# Dyno_Tiva_Shield.net
KiCad netlist of a schematic drawn in EAGLE
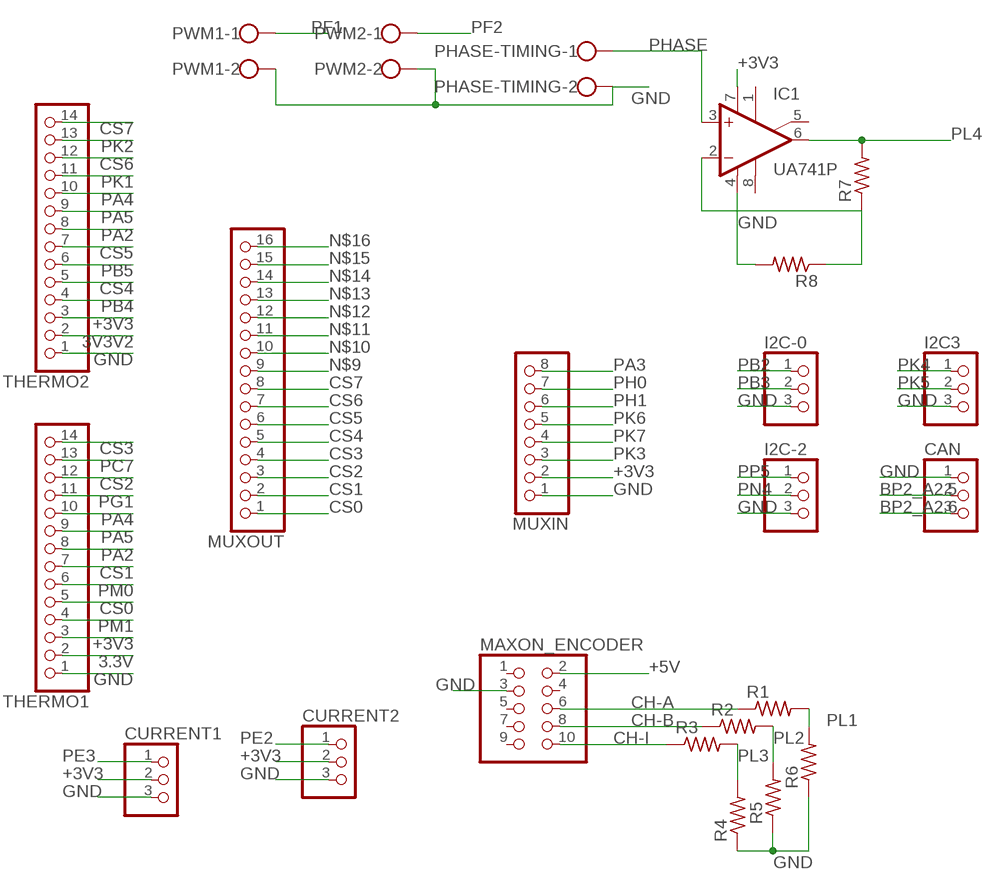
[diagram p0: schematic, sheet 1]
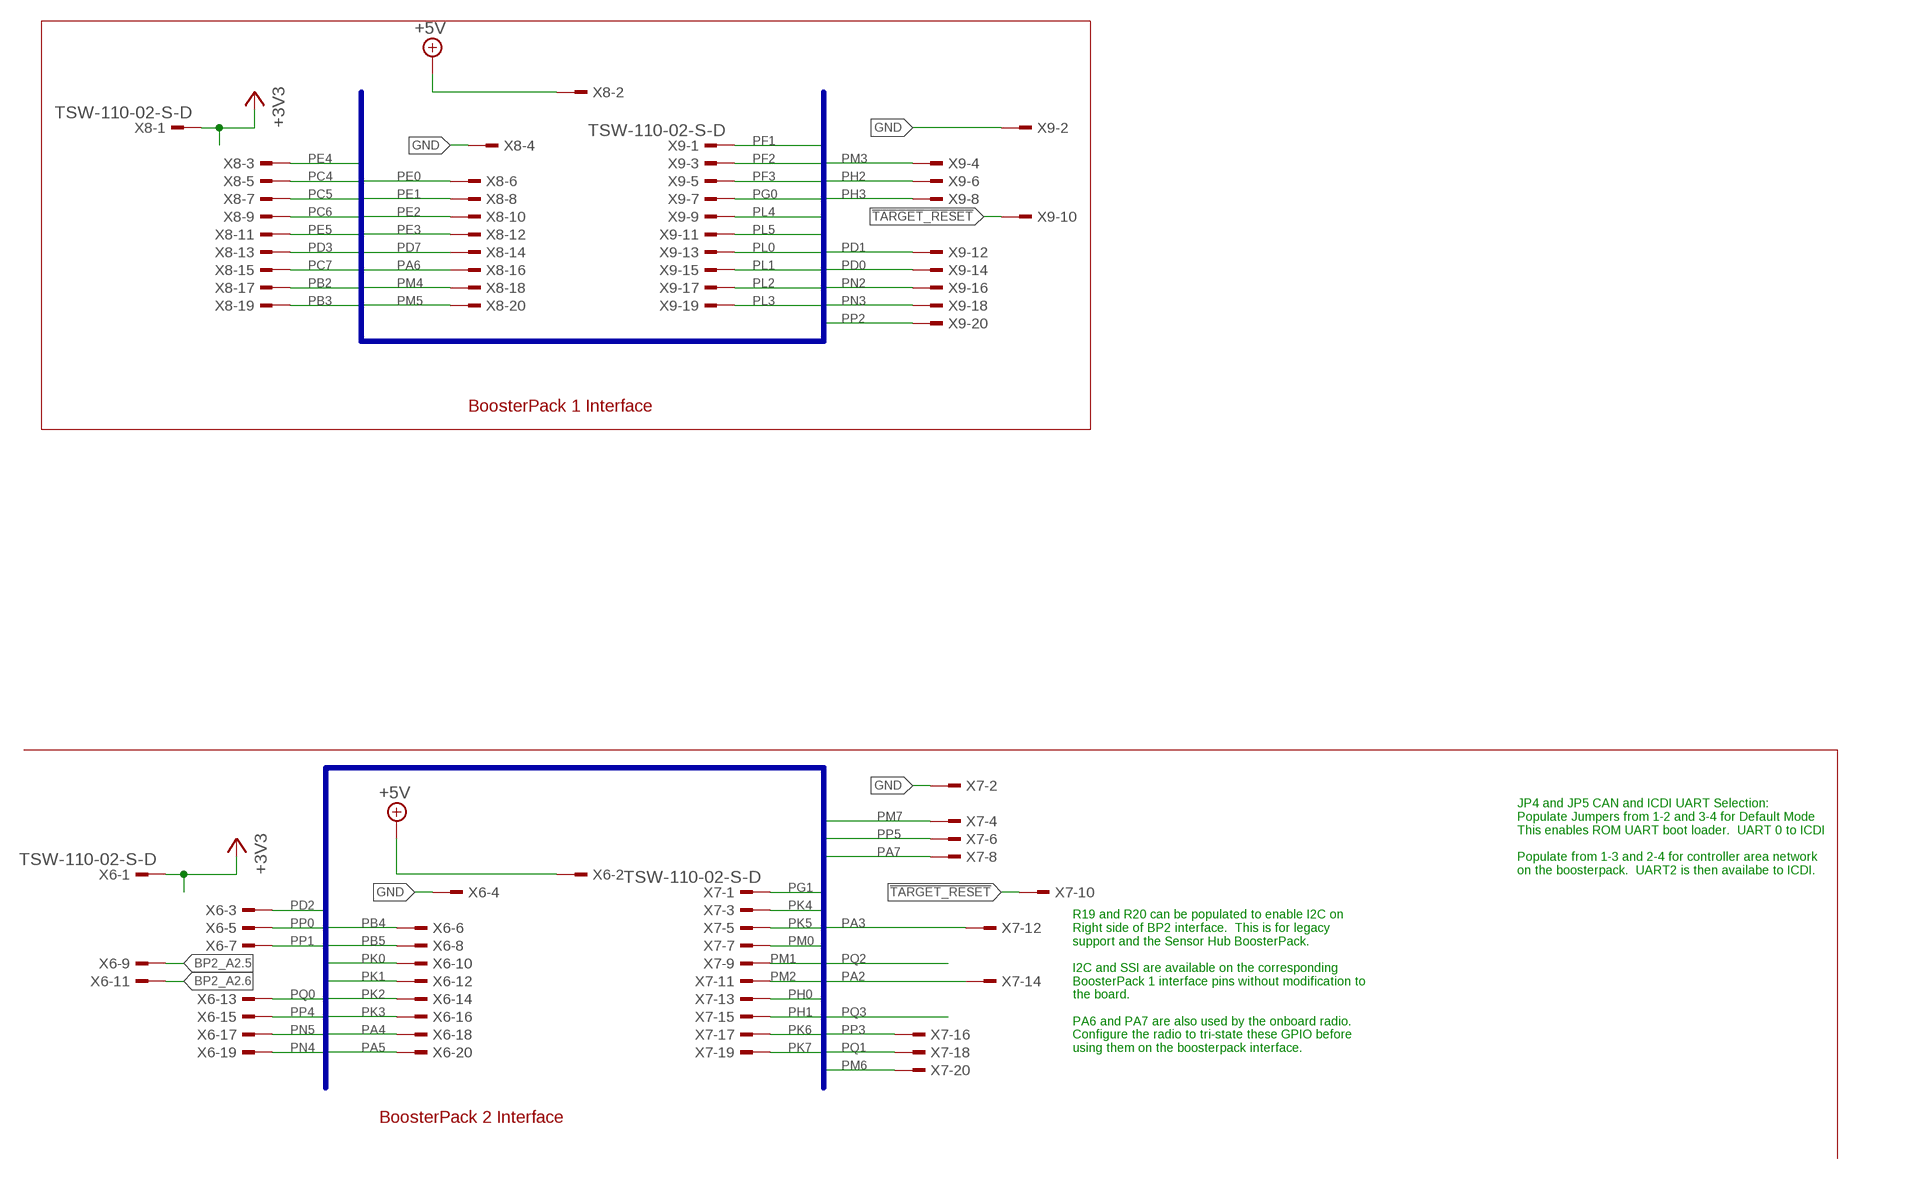
[diagram p1: schematic, sheet 2]

(export (version "E")
  (design (tool "Eeschema 10.0.6"))
  (components
    (comp (ref "X6")
      (value "TSW-110-02-S-D")
      (footprint "eagle-import:TSW-110-02-S-D")
      (fields (field (name "GNUM") "G22-THSTK-2X10-BAC"))
      (libsource (lib "eagle-import") (part "TSW-110-02-S-D"))
    )
    (comp (ref "X7")
      (value "TSW-110-02-S-D")
      (footprint "eagle-import:TSW-110-02-S-D")
      (fields (field (name "GNUM") "G22-THSTK-2X10-BAC"))
      (libsource (lib "eagle-import") (part "TSW-110-02-S-D"))
    )
    (comp (ref "X8")
      (value "TSW-110-02-S-D")
      (footprint "eagle-import:TSW-110-02-S-D")
      (fields (field (name "GNUM") "G22-THSTK-2X10-BAC"))
      (libsource (lib "eagle-import") (part "TSW-110-02-S-D"))
    )
    (comp (ref "X9")
      (value "TSW-110-02-S-D")
      (footprint "eagle-import:TSW-110-02-S-D")
      (fields (field (name "GNUM") "G22-THSTK-2X10-BAC"))
      (libsource (lib "eagle-import") (part "TSW-110-02-S-D"))
    )
    (comp (ref "CAN")
      (value "PINHD-1X3")
      (footprint "eagle-import:1X03")
      (libsource (lib "eagle-import") (part "PINHD-1X3"))
    )
    (comp (ref "CURRENT1")
      (value "PINHD-1X3")
      (footprint "eagle-import:1X03")
      (libsource (lib "eagle-import") (part "PINHD-1X3"))
    )
    (comp (ref "CURRENT2")
      (value "PINHD-1X3")
      (footprint "eagle-import:1X03")
      (libsource (lib "eagle-import") (part "PINHD-1X3"))
    )
    (comp (ref "I2C-0")
      (value "PINHD-1X3")
      (footprint "eagle-import:1X03")
      (libsource (lib "eagle-import") (part "PINHD-1X3"))
    )
    (comp (ref "I2C-2")
      (value "PINHD-1X3")
      (footprint "eagle-import:1X03")
      (libsource (lib "eagle-import") (part "PINHD-1X3"))
    )
    (comp (ref "I2C3")
      (value "PINHD-1X3")
      (footprint "eagle-import:1X03")
      (libsource (lib "eagle-import") (part "PINHD-1X3"))
    )
    (comp (ref "IC1")
      (value "UA741P")
      (footprint "eagle-import:DIL08")
      (libsource (lib "eagle-import") (part "741PUA"))
    )
    (comp (ref "MAXON_ENCODER")
      (value "PINHD-2X5")
      (footprint "eagle-import:2X05")
      (libsource (lib "eagle-import") (part "PINHD-2X5"))
    )
    (comp (ref "MUXIN")
      (value "PINHD-1X8")
      (footprint "eagle-import:1X08")
      (libsource (lib "eagle-import") (part "PINHD-1X8"))
    )
    (comp (ref "MUXOUT")
      (value "PINHD-1X16")
      (footprint "eagle-import:1X16")
      (libsource (lib "eagle-import") (part "PINHD-1X16"))
    )
    (comp (ref "PHASE-TIMING")
      (value "W237-102")
      (footprint "eagle-import:W237-102")
      (fields (field (name "MPN") "237-102"))
      (libsource (lib "eagle-import") (part "W237-102"))
    )
    (comp (ref "PWM1")
      (value "W237-102")
      (footprint "eagle-import:W237-102")
      (fields (field (name "MPN") "237-102"))
      (libsource (lib "eagle-import") (part "W237-102"))
    )
    (comp (ref "PWM2")
      (value "W237-102")
      (footprint "eagle-import:W237-102")
      (fields (field (name "MPN") "237-102"))
      (libsource (lib "eagle-import") (part "W237-102"))
    )
    (comp (ref "R1")
      (value "R-US_M0805")
      (footprint "eagle-import:M0805")
      (libsource (lib "eagle-import") (part "R-US_M0805"))
    )
    (comp (ref "R2")
      (value "R-US_M0805")
      (footprint "eagle-import:M0805")
      (libsource (lib "eagle-import") (part "R-US_M0805"))
    )
    (comp (ref "R3")
      (value "R-US_M0805")
      (footprint "eagle-import:M0805")
      (libsource (lib "eagle-import") (part "R-US_M0805"))
    )
    (comp (ref "R4")
      (value "R-US_M0805")
      (footprint "eagle-import:M0805")
      (libsource (lib "eagle-import") (part "R-US_M0805"))
    )
    (comp (ref "R5")
      (value "R-US_M0805")
      (footprint "eagle-import:M0805")
      (libsource (lib "eagle-import") (part "R-US_M0805"))
    )
    (comp (ref "R6")
      (value "R-US_M0805")
      (footprint "eagle-import:M0805")
      (libsource (lib "eagle-import") (part "R-US_M0805"))
    )
    (comp (ref "R7")
      (value "R-US_M0805")
      (footprint "eagle-import:M0805")
      (libsource (lib "eagle-import") (part "R-US_M0805"))
    )
    (comp (ref "R8")
      (value "R-US_M0805")
      (footprint "eagle-import:M0805")
      (libsource (lib "eagle-import") (part "R-US_M0805"))
    )
    (comp (ref "THERMO1")
      (value "PINHD-1X14")
      (footprint "eagle-import:1X14")
      (libsource (lib "eagle-import") (part "PINHD-1X14"))
    )
    (comp (ref "THERMO2")
      (value "PINHD-1X14")
      (footprint "eagle-import:1X14")
      (libsource (lib "eagle-import") (part "PINHD-1X14"))
    )
  )
  (nets
    (net (code "1") (name "+3V3") (class "Default")
      (node (ref "CURRENT1") (pin "2") (pinfunction "2_2") (pintype "passive"))
      (node (ref "CURRENT2") (pin "2") (pinfunction "2_2") (pintype "passive"))
      (node (ref "IC1") (pin "7") (pinfunction "V+_7") (pintype "power_in"))
      (node (ref "MUXIN") (pin "2") (pinfunction "2_2") (pintype "passive"))
      (node (ref "THERMO1") (pin "3") (pinfunction "3_3") (pintype "passive"))
      (node (ref "THERMO2") (pin "3") (pinfunction "3_3") (pintype "passive"))
      (node (ref "X6") (pin "1") (pinfunction "1_1") (pintype "passive"))
      (node (ref "X8") (pin "1") (pinfunction "1_1") (pintype "passive"))
    )
    (net (code "2") (name "+5V") (class "Default")
      (node (ref "MAXON_ENCODER") (pin "2") (pinfunction "2_2") (pintype "passive"))
      (node (ref "X6") (pin "2") (pinfunction "1_2") (pintype "passive"))
      (node (ref "X8") (pin "2") (pinfunction "1_2") (pintype "passive"))
    )
    (net (code "3") (name "3.3V") (class "Default")
      (node (ref "THERMO1") (pin "2") (pinfunction "2_2") (pintype "passive"))
    )
    (net (code "4") (name "3V3V2") (class "Default")
      (node (ref "THERMO2") (pin "2") (pinfunction "2_2") (pintype "passive"))
    )
    (net (code "5") (name "BP2_A2.5") (class "Default")
      (node (ref "CAN") (pin "2") (pinfunction "2_2") (pintype "passive"))
      (node (ref "X6") (pin "9") (pinfunction "1_9") (pintype "passive"))
    )
    (net (code "6") (name "BP2_A2.6") (class "Default")
      (node (ref "CAN") (pin "3") (pinfunction "3_3") (pintype "passive"))
      (node (ref "X6") (pin "11") (pinfunction "1_11") (pintype "passive"))
    )
    (net (code "7") (name "CH-A") (class "Default")
      (node (ref "MAXON_ENCODER") (pin "6") (pinfunction "6_6") (pintype "passive"))
      (node (ref "R1") (pin "1") (pinfunction "1_1") (pintype "passive"))
    )
    (net (code "8") (name "CH-B") (class "Default")
      (node (ref "MAXON_ENCODER") (pin "8") (pinfunction "8_8") (pintype "passive"))
      (node (ref "R2") (pin "1") (pinfunction "1_1") (pintype "passive"))
    )
    (net (code "9") (name "CH-I") (class "Default")
      (node (ref "MAXON_ENCODER") (pin "10") (pinfunction "10_10") (pintype "passive"))
      (node (ref "R3") (pin "1") (pinfunction "1_1") (pintype "passive"))
    )
    (net (code "10") (name "CS0") (class "Default")
      (node (ref "MUXOUT") (pin "1") (pinfunction "1_1") (pintype "passive"))
      (node (ref "THERMO1") (pin "5") (pinfunction "5_5") (pintype "passive"))
    )
    (net (code "11") (name "CS1") (class "Default")
      (node (ref "MUXOUT") (pin "2") (pinfunction "2_2") (pintype "passive"))
      (node (ref "THERMO1") (pin "7") (pinfunction "7_7") (pintype "passive"))
    )
    (net (code "12") (name "CS2") (class "Default")
      (node (ref "MUXOUT") (pin "3") (pinfunction "3_3") (pintype "passive"))
      (node (ref "THERMO1") (pin "12") (pinfunction "12_12") (pintype "passive"))
    )
    (net (code "13") (name "CS3") (class "Default")
      (node (ref "MUXOUT") (pin "4") (pinfunction "4_4") (pintype "passive"))
      (node (ref "THERMO1") (pin "14") (pinfunction "14_14") (pintype "passive"))
    )
    (net (code "14") (name "CS4") (class "Default")
      (node (ref "MUXOUT") (pin "5") (pinfunction "5_5") (pintype "passive"))
      (node (ref "THERMO2") (pin "5") (pinfunction "5_5") (pintype "passive"))
    )
    (net (code "15") (name "CS5") (class "Default")
      (node (ref "MUXOUT") (pin "6") (pinfunction "6_6") (pintype "passive"))
      (node (ref "THERMO2") (pin "7") (pinfunction "7_7") (pintype "passive"))
    )
    (net (code "16") (name "CS6") (class "Default")
      (node (ref "MUXOUT") (pin "7") (pinfunction "7_7") (pintype "passive"))
      (node (ref "THERMO2") (pin "12") (pinfunction "12_12") (pintype "passive"))
    )
    (net (code "17") (name "CS7") (class "Default")
      (node (ref "MUXOUT") (pin "8") (pinfunction "8_8") (pintype "passive"))
      (node (ref "THERMO2") (pin "14") (pinfunction "14_14") (pintype "passive"))
    )
    (net (code "18") (name "GND") (class "Default")
      (node (ref "CAN") (pin "1") (pinfunction "1_1") (pintype "passive"))
      (node (ref "CURRENT1") (pin "3") (pinfunction "3_3") (pintype "passive"))
      (node (ref "CURRENT2") (pin "3") (pinfunction "3_3") (pintype "passive"))
      (node (ref "I2C-0") (pin "3") (pinfunction "3_3") (pintype "passive"))
      (node (ref "I2C-2") (pin "3") (pinfunction "3_3") (pintype "passive"))
      (node (ref "I2C3") (pin "3") (pinfunction "3_3") (pintype "passive"))
      (node (ref "IC1") (pin "4") (pinfunction "V-_4") (pintype "power_in"))
      (node (ref "MAXON_ENCODER") (pin "3") (pinfunction "3_3") (pintype "passive"))
      (node (ref "MUXIN") (pin "1") (pinfunction "1_1") (pintype "passive"))
      (node (ref "PHASE-TIMING") (pin "2") (pinfunction "KL_2") (pintype "passive"))
      (node (ref "PWM1") (pin "2") (pinfunction "KL_2") (pintype "passive"))
      (node (ref "PWM2") (pin "2") (pinfunction "KL_2") (pintype "passive"))
      (node (ref "R4") (pin "1") (pinfunction "1_1") (pintype "passive"))
      (node (ref "R5") (pin "1") (pinfunction "1_1") (pintype "passive"))
      (node (ref "R6") (pin "1") (pinfunction "1_1") (pintype "passive"))
      (node (ref "R8") (pin "2") (pinfunction "2_2") (pintype "passive"))
      (node (ref "THERMO1") (pin "1") (pinfunction "1_1") (pintype "passive"))
      (node (ref "THERMO2") (pin "1") (pinfunction "1_1") (pintype "passive"))
      (node (ref "X6") (pin "4") (pinfunction "1_4") (pintype "passive"))
      (node (ref "X7") (pin "2") (pinfunction "1_2") (pintype "passive"))
      (node (ref "X8") (pin "4") (pinfunction "1_4") (pintype "passive"))
      (node (ref "X9") (pin "2") (pinfunction "1_2") (pintype "passive"))
    )
    (net (code "19") (name "N$9") (class "Default")
      (node (ref "MUXOUT") (pin "9") (pinfunction "9_9") (pintype "passive"))
    )
    (net (code "20") (name "N$10") (class "Default")
      (node (ref "MUXOUT") (pin "10") (pinfunction "10_10") (pintype "passive"))
    )
    (net (code "21") (name "N$11") (class "Default")
      (node (ref "MUXOUT") (pin "11") (pinfunction "11_11") (pintype "passive"))
    )
    (net (code "22") (name "N$12") (class "Default")
      (node (ref "MUXOUT") (pin "12") (pinfunction "12_12") (pintype "passive"))
    )
    (net (code "23") (name "N$13") (class "Default")
      (node (ref "MUXOUT") (pin "13") (pinfunction "13_13") (pintype "passive"))
    )
    (net (code "24") (name "N$14") (class "Default")
      (node (ref "MUXOUT") (pin "14") (pinfunction "14_14") (pintype "passive"))
    )
    (net (code "25") (name "N$15") (class "Default")
      (node (ref "MUXOUT") (pin "15") (pinfunction "15_15") (pintype "passive"))
    )
    (net (code "26") (name "N$16") (class "Default")
      (node (ref "MUXOUT") (pin "16") (pinfunction "16_16") (pintype "passive"))
    )
    (net (code "27") (name "Net-(IC1--IN)") (class "Default")
      (node (ref "IC1") (pin "2") (pinfunction "-IN_2") (pintype "input"))
      (node (ref "R7") (pin "1") (pinfunction "1_1") (pintype "passive"))
      (node (ref "R8") (pin "1") (pinfunction "1_1") (pintype "passive"))
    )
    (net (code "28") (name "PA2") (class "Default")
      (node (ref "THERMO1") (pin "8") (pinfunction "8_8") (pintype "passive"))
      (node (ref "THERMO2") (pin "8") (pinfunction "8_8") (pintype "passive"))
      (node (ref "X7") (pin "14") (pinfunction "1_14") (pintype "passive"))
    )
    (net (code "29") (name "PA3") (class "Default")
      (node (ref "MUXIN") (pin "8") (pinfunction "8_8") (pintype "passive"))
      (node (ref "X7") (pin "12") (pinfunction "1_12") (pintype "passive"))
    )
    (net (code "30") (name "PA4") (class "Default")
      (node (ref "THERMO1") (pin "10") (pinfunction "10_10") (pintype "passive"))
      (node (ref "THERMO2") (pin "10") (pinfunction "10_10") (pintype "passive"))
      (node (ref "X6") (pin "18") (pinfunction "1_18") (pintype "passive"))
    )
    (net (code "31") (name "PA5") (class "Default")
      (node (ref "THERMO1") (pin "9") (pinfunction "9_9") (pintype "passive"))
      (node (ref "THERMO2") (pin "9") (pinfunction "9_9") (pintype "passive"))
      (node (ref "X6") (pin "20") (pinfunction "1_20") (pintype "passive"))
    )
    (net (code "32") (name "PA6") (class "Default")
      (node (ref "X8") (pin "16") (pinfunction "1_16") (pintype "passive"))
    )
    (net (code "33") (name "PA7") (class "Default")
      (node (ref "X7") (pin "8") (pinfunction "1_8") (pintype "passive"))
    )
    (net (code "34") (name "PB2") (class "Default")
      (node (ref "I2C-0") (pin "1") (pinfunction "1_1") (pintype "passive"))
      (node (ref "X8") (pin "17") (pinfunction "1_17") (pintype "passive"))
    )
    (net (code "35") (name "PB3") (class "Default")
      (node (ref "I2C-0") (pin "2") (pinfunction "2_2") (pintype "passive"))
      (node (ref "X8") (pin "19") (pinfunction "1_19") (pintype "passive"))
    )
    (net (code "36") (name "PB4") (class "Default")
      (node (ref "THERMO2") (pin "4") (pinfunction "4_4") (pintype "passive"))
      (node (ref "X6") (pin "6") (pinfunction "1_6") (pintype "passive"))
    )
    (net (code "37") (name "PB5") (class "Default")
      (node (ref "THERMO2") (pin "6") (pinfunction "6_6") (pintype "passive"))
      (node (ref "X6") (pin "8") (pinfunction "1_8") (pintype "passive"))
    )
    (net (code "38") (name "PC4") (class "Default")
      (node (ref "X8") (pin "5") (pinfunction "1_5") (pintype "passive"))
    )
    (net (code "39") (name "PC5") (class "Default")
      (node (ref "X8") (pin "7") (pinfunction "1_7") (pintype "passive"))
    )
    (net (code "40") (name "PC6") (class "Default")
      (node (ref "X8") (pin "9") (pinfunction "1_9") (pintype "passive"))
    )
    (net (code "41") (name "PC7") (class "Default")
      (node (ref "THERMO1") (pin "13") (pinfunction "13_13") (pintype "passive"))
      (node (ref "X8") (pin "15") (pinfunction "1_15") (pintype "passive"))
    )
    (net (code "42") (name "PD0") (class "Default")
      (node (ref "X9") (pin "14") (pinfunction "1_14") (pintype "passive"))
    )
    (net (code "43") (name "PD1") (class "Default")
      (node (ref "X9") (pin "12") (pinfunction "1_12") (pintype "passive"))
    )
    (net (code "44") (name "PD2") (class "Default")
      (node (ref "X6") (pin "3") (pinfunction "1_3") (pintype "passive"))
    )
    (net (code "45") (name "PD3") (class "Default")
      (node (ref "X8") (pin "13") (pinfunction "1_13") (pintype "passive"))
    )
    (net (code "46") (name "PD7") (class "Default")
      (node (ref "X8") (pin "14") (pinfunction "1_14") (pintype "passive"))
    )
    (net (code "47") (name "PE0") (class "Default")
      (node (ref "X8") (pin "6") (pinfunction "1_6") (pintype "passive"))
    )
    (net (code "48") (name "PE1") (class "Default")
      (node (ref "X8") (pin "8") (pinfunction "1_8") (pintype "passive"))
    )
    (net (code "49") (name "PE2") (class "Default")
      (node (ref "CURRENT2") (pin "1") (pinfunction "1_1") (pintype "passive"))
      (node (ref "X8") (pin "10") (pinfunction "1_10") (pintype "passive"))
    )
    (net (code "50") (name "PE3") (class "Default")
      (node (ref "CURRENT1") (pin "1") (pinfunction "1_1") (pintype "passive"))
      (node (ref "X8") (pin "12") (pinfunction "1_12") (pintype "passive"))
    )
    (net (code "51") (name "PE4") (class "Default")
      (node (ref "X8") (pin "3") (pinfunction "1_3") (pintype "passive"))
    )
    (net (code "52") (name "PE5") (class "Default")
      (node (ref "X8") (pin "11") (pinfunction "1_11") (pintype "passive"))
    )
    (net (code "53") (name "PF1") (class "Default")
      (node (ref "PWM1") (pin "1") (pinfunction "KL_1") (pintype "passive"))
      (node (ref "X9") (pin "1") (pinfunction "1_1") (pintype "passive"))
    )
    (net (code "54") (name "PF2") (class "Default")
      (node (ref "PWM2") (pin "1") (pinfunction "KL_1") (pintype "passive"))
      (node (ref "X9") (pin "3") (pinfunction "1_3") (pintype "passive"))
    )
    (net (code "55") (name "PF3") (class "Default")
      (node (ref "X9") (pin "5") (pinfunction "1_5") (pintype "passive"))
    )
    (net (code "56") (name "PG0") (class "Default")
      (node (ref "X9") (pin "7") (pinfunction "1_7") (pintype "passive"))
    )
    (net (code "57") (name "PG1") (class "Default")
      (node (ref "THERMO1") (pin "11") (pinfunction "11_11") (pintype "passive"))
      (node (ref "X7") (pin "1") (pinfunction "1_1") (pintype "passive"))
    )
    (net (code "58") (name "PH0") (class "Default")
      (node (ref "MUXIN") (pin "7") (pinfunction "7_7") (pintype "passive"))
      (node (ref "X7") (pin "13") (pinfunction "1_13") (pintype "passive"))
    )
    (net (code "59") (name "PH1") (class "Default")
      (node (ref "MUXIN") (pin "6") (pinfunction "6_6") (pintype "passive"))
      (node (ref "X7") (pin "15") (pinfunction "1_15") (pintype "passive"))
    )
    (net (code "60") (name "PH2") (class "Default")
      (node (ref "X9") (pin "6") (pinfunction "1_6") (pintype "passive"))
    )
    (net (code "61") (name "PH3") (class "Default")
      (node (ref "X9") (pin "8") (pinfunction "1_8") (pintype "passive"))
    )
    (net (code "62") (name "PHASE") (class "Default")
      (node (ref "IC1") (pin "3") (pinfunction "+IN_3") (pintype "input"))
      (node (ref "PHASE-TIMING") (pin "1") (pinfunction "KL_1") (pintype "passive"))
    )
    (net (code "63") (name "PK0") (class "Default")
      (node (ref "X6") (pin "10") (pinfunction "1_10") (pintype "passive"))
    )
    (net (code "64") (name "PK1") (class "Default")
      (node (ref "THERMO2") (pin "11") (pinfunction "11_11") (pintype "passive"))
      (node (ref "X6") (pin "12") (pinfunction "1_12") (pintype "passive"))
    )
    (net (code "65") (name "PK2") (class "Default")
      (node (ref "THERMO2") (pin "13") (pinfunction "13_13") (pintype "passive"))
      (node (ref "X6") (pin "14") (pinfunction "1_14") (pintype "passive"))
    )
    (net (code "66") (name "PK3") (class "Default")
      (node (ref "MUXIN") (pin "3") (pinfunction "3_3") (pintype "passive"))
      (node (ref "X6") (pin "16") (pinfunction "1_16") (pintype "passive"))
    )
    (net (code "67") (name "PK4") (class "Default")
      (node (ref "I2C3") (pin "1") (pinfunction "1_1") (pintype "passive"))
      (node (ref "X7") (pin "3") (pinfunction "1_3") (pintype "passive"))
    )
    (net (code "68") (name "PK5") (class "Default")
      (node (ref "I2C3") (pin "2") (pinfunction "2_2") (pintype "passive"))
      (node (ref "X7") (pin "5") (pinfunction "1_5") (pintype "passive"))
    )
    (net (code "69") (name "PK6") (class "Default")
      (node (ref "MUXIN") (pin "5") (pinfunction "5_5") (pintype "passive"))
      (node (ref "X7") (pin "17") (pinfunction "1_17") (pintype "passive"))
    )
    (net (code "70") (name "PK7") (class "Default")
      (node (ref "MUXIN") (pin "4") (pinfunction "4_4") (pintype "passive"))
      (node (ref "X7") (pin "19") (pinfunction "1_19") (pintype "passive"))
    )
    (net (code "71") (name "PL0") (class "Default")
      (node (ref "X9") (pin "13") (pinfunction "1_13") (pintype "passive"))
    )
    (net (code "72") (name "PL1") (class "Default")
      (node (ref "R1") (pin "2") (pinfunction "2_2") (pintype "passive"))
      (node (ref "R6") (pin "2") (pinfunction "2_2") (pintype "passive"))
      (node (ref "X9") (pin "15") (pinfunction "1_15") (pintype "passive"))
    )
    (net (code "73") (name "PL2") (class "Default")
      (node (ref "R2") (pin "2") (pinfunction "2_2") (pintype "passive"))
      (node (ref "R5") (pin "2") (pinfunction "2_2") (pintype "passive"))
      (node (ref "X9") (pin "17") (pinfunction "1_17") (pintype "passive"))
    )
    (net (code "74") (name "PL3") (class "Default")
      (node (ref "R3") (pin "2") (pinfunction "2_2") (pintype "passive"))
      (node (ref "R4") (pin "2") (pinfunction "2_2") (pintype "passive"))
      (node (ref "X9") (pin "19") (pinfunction "1_19") (pintype "passive"))
    )
    (net (code "75") (name "PL4") (class "Default")
      (node (ref "IC1") (pin "6") (pinfunction "OUT_6") (pintype "output"))
      (node (ref "R7") (pin "2") (pinfunction "2_2") (pintype "passive"))
      (node (ref "X9") (pin "9") (pinfunction "1_9") (pintype "passive"))
    )
    (net (code "76") (name "PL5") (class "Default")
      (node (ref "X9") (pin "11") (pinfunction "1_11") (pintype "passive"))
    )
    (net (code "77") (name "PM0") (class "Default")
      (node (ref "THERMO1") (pin "6") (pinfunction "6_6") (pintype "passive"))
      (node (ref "X7") (pin "7") (pinfunction "1_7") (pintype "passive"))
    )
    (net (code "78") (name "PM1") (class "Default")
      (node (ref "THERMO1") (pin "4") (pinfunction "4_4") (pintype "passive"))
      (node (ref "X7") (pin "9") (pinfunction "1_9") (pintype "passive"))
    )
    (net (code "79") (name "PM2") (class "Default")
      (node (ref "X7") (pin "11") (pinfunction "1_11") (pintype "passive"))
    )
    (net (code "80") (name "PM3") (class "Default")
      (node (ref "X9") (pin "4") (pinfunction "1_4") (pintype "passive"))
    )
    (net (code "81") (name "PM4") (class "Default")
      (node (ref "X8") (pin "18") (pinfunction "1_18") (pintype "passive"))
    )
    (net (code "82") (name "PM5") (class "Default")
      (node (ref "X8") (pin "20") (pinfunction "1_20") (pintype "passive"))
    )
    (net (code "83") (name "PM6") (class "Default")
      (node (ref "X7") (pin "20") (pinfunction "1_20") (pintype "passive"))
    )
    (net (code "84") (name "PM7") (class "Default")
      (node (ref "X7") (pin "4") (pinfunction "1_4") (pintype "passive"))
    )
    (net (code "85") (name "PN2") (class "Default")
      (node (ref "X9") (pin "16") (pinfunction "1_16") (pintype "passive"))
    )
    (net (code "86") (name "PN3") (class "Default")
      (node (ref "X9") (pin "18") (pinfunction "1_18") (pintype "passive"))
    )
    (net (code "87") (name "PN4") (class "Default")
      (node (ref "I2C-2") (pin "2") (pinfunction "2_2") (pintype "passive"))
      (node (ref "X6") (pin "19") (pinfunction "1_19") (pintype "passive"))
    )
    (net (code "88") (name "PN5") (class "Default")
      (node (ref "X6") (pin "17") (pinfunction "1_17") (pintype "passive"))
    )
    (net (code "89") (name "PP0") (class "Default")
      (node (ref "X6") (pin "5") (pinfunction "1_5") (pintype "passive"))
    )
    (net (code "90") (name "PP1") (class "Default")
      (node (ref "X6") (pin "7") (pinfunction "1_7") (pintype "passive"))
    )
    (net (code "91") (name "PP2") (class "Default")
      (node (ref "X9") (pin "20") (pinfunction "1_20") (pintype "passive"))
    )
    (net (code "92") (name "PP3") (class "Default")
      (node (ref "X7") (pin "16") (pinfunction "1_16") (pintype "passive"))
    )
    (net (code "93") (name "PP4") (class "Default")
      (node (ref "X6") (pin "15") (pinfunction "1_15") (pintype "passive"))
    )
    (net (code "94") (name "PP5") (class "Default")
      (node (ref "I2C-2") (pin "1") (pinfunction "1_1") (pintype "passive"))
      (node (ref "X7") (pin "6") (pinfunction "1_6") (pintype "passive"))
    )
    (net (code "95") (name "PQ0") (class "Default")
      (node (ref "X6") (pin "13") (pinfunction "1_13") (pintype "passive"))
    )
    (net (code "96") (name "PQ1") (class "Default")
      (node (ref "X7") (pin "18") (pinfunction "1_18") (pintype "passive"))
    )
    (net (code "99") (name "unconnected-(IC1-ON1-Pad1)") (class "Default")
      (node (ref "IC1") (pin "1") (pinfunction "ON1_1") (pintype "passive"))
    )
    (net (code "100") (name "unconnected-(IC1-ON2-Pad5)") (class "Default")
      (node (ref "IC1") (pin "5") (pinfunction "ON2_5") (pintype "passive"))
    )
    (net (code "101") (name "unconnected-(IC1-OPT-Pad8)") (class "Default")
      (node (ref "IC1") (pin "8") (pinfunction "OPT_8") (pintype "passive"))
    )
    (net (code "102") (name "unconnected-(MAXON_ENCODER-Pad1)") (class "Default")
      (node (ref "MAXON_ENCODER") (pin "1") (pinfunction "1_1") (pintype "passive"))
    )
    (net (code "103") (name "unconnected-(MAXON_ENCODER-Pad4)") (class "Default")
      (node (ref "MAXON_ENCODER") (pin "4") (pinfunction "4_4") (pintype "passive"))
    )
    (net (code "104") (name "unconnected-(MAXON_ENCODER-Pad5)") (class "Default")
      (node (ref "MAXON_ENCODER") (pin "5") (pinfunction "5_5") (pintype "passive"))
    )
    (net (code "105") (name "unconnected-(MAXON_ENCODER-Pad7)") (class "Default")
      (node (ref "MAXON_ENCODER") (pin "7") (pinfunction "7_7") (pintype "passive"))
    )
    (net (code "106") (name "unconnected-(MAXON_ENCODER-Pad9)") (class "Default")
      (node (ref "MAXON_ENCODER") (pin "9") (pinfunction "9_9") (pintype "passive"))
    )
    (net (code "107") (name "~{TARGET_RESET}") (class "Default")
      (node (ref "X7") (pin "10") (pinfunction "1_10") (pintype "passive"))
      (node (ref "X9") (pin "10") (pinfunction "1_10") (pintype "passive"))
    )
  )
)
